# KeyMatrix.net
KiCad netlist of a schematic drawn in Altium Designer
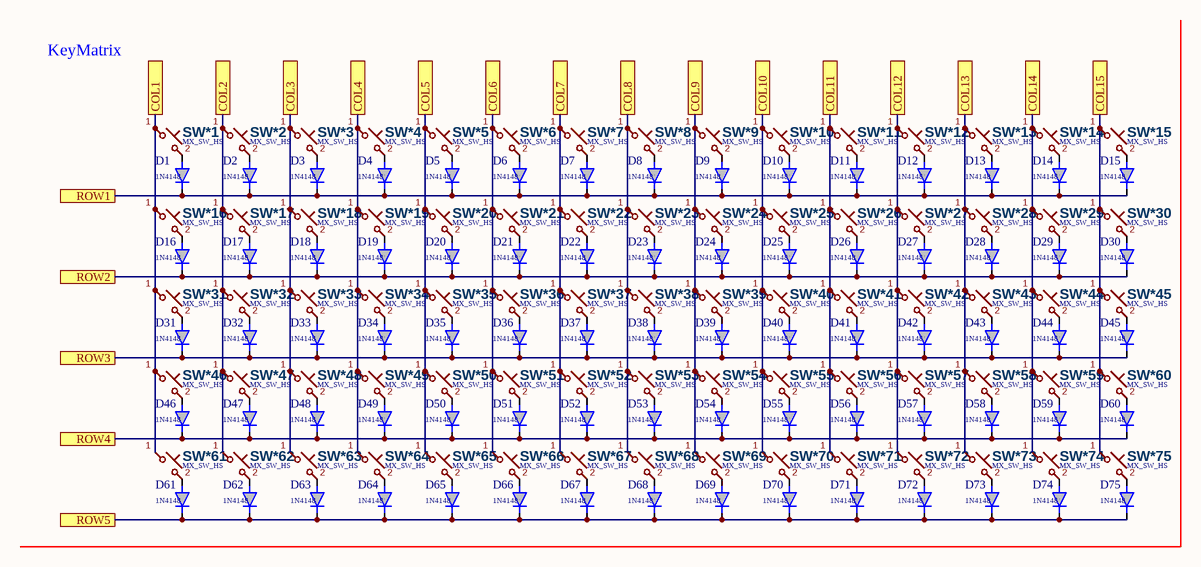
[diagram p0: KeyMatrix.SchDoc]

(export (version "E")
  (design (tool "Eeschema 10.0.6"))
  (components
    (comp (ref "D1")
      (value "1N4148")
      (footprint "SOD3716X135N")
      (description "Small Signal Fast Switching Diode")
      (fields (field (name "MANUFACTURER_PART_NUMBER") "1N4148(SOD-123)"))
      (libsource (lib "1N4148_SOD-123_") (part "1N4148_SOD-123_"))
    )
    (comp (ref "D2")
      (value "1N4148")
      (footprint "SOD3716X135N")
      (description "Small Signal Fast Switching Diode")
      (fields (field (name "MANUFACTURER_PART_NUMBER") "1N4148(SOD-123)"))
      (libsource (lib "1N4148_SOD-123_") (part "1N4148_SOD-123_"))
    )
    (comp (ref "D3")
      (value "1N4148")
      (footprint "SOD3716X135N")
      (description "Small Signal Fast Switching Diode")
      (fields (field (name "MANUFACTURER_PART_NUMBER") "1N4148(SOD-123)"))
      (libsource (lib "1N4148_SOD-123_") (part "1N4148_SOD-123_"))
    )
    (comp (ref "D4")
      (value "1N4148")
      (footprint "SOD3716X135N")
      (description "Small Signal Fast Switching Diode")
      (fields (field (name "MANUFACTURER_PART_NUMBER") "1N4148(SOD-123)"))
      (libsource (lib "1N4148_SOD-123_") (part "1N4148_SOD-123_"))
    )
    (comp (ref "D5")
      (value "1N4148")
      (footprint "SOD3716X135N")
      (description "Small Signal Fast Switching Diode")
      (fields (field (name "MANUFACTURER_PART_NUMBER") "1N4148(SOD-123)"))
      (libsource (lib "1N4148_SOD-123_") (part "1N4148_SOD-123_"))
    )
    (comp (ref "D6")
      (value "1N4148")
      (footprint "SOD3716X135N")
      (description "Small Signal Fast Switching Diode")
      (fields (field (name "MANUFACTURER_PART_NUMBER") "1N4148(SOD-123)"))
      (libsource (lib "1N4148_SOD-123_") (part "1N4148_SOD-123_"))
    )
    (comp (ref "D7")
      (value "1N4148")
      (footprint "SOD3716X135N")
      (description "Small Signal Fast Switching Diode")
      (fields (field (name "MANUFACTURER_PART_NUMBER") "1N4148(SOD-123)"))
      (libsource (lib "1N4148_SOD-123_") (part "1N4148_SOD-123_"))
    )
    (comp (ref "D8")
      (value "1N4148")
      (footprint "SOD3716X135N")
      (description "Small Signal Fast Switching Diode")
      (fields (field (name "MANUFACTURER_PART_NUMBER") "1N4148(SOD-123)"))
      (libsource (lib "1N4148_SOD-123_") (part "1N4148_SOD-123_"))
    )
    (comp (ref "D9")
      (value "1N4148")
      (footprint "SOD3716X135N")
      (description "Small Signal Fast Switching Diode")
      (fields (field (name "MANUFACTURER_PART_NUMBER") "1N4148(SOD-123)"))
      (libsource (lib "1N4148_SOD-123_") (part "1N4148_SOD-123_"))
    )
    (comp (ref "D10")
      (value "1N4148")
      (footprint "SOD3716X135N")
      (description "Small Signal Fast Switching Diode")
      (fields (field (name "MANUFACTURER_PART_NUMBER") "1N4148(SOD-123)"))
      (libsource (lib "1N4148_SOD-123_") (part "1N4148_SOD-123_"))
    )
    (comp (ref "D11")
      (value "1N4148")
      (footprint "SOD3716X135N")
      (description "Small Signal Fast Switching Diode")
      (fields (field (name "MANUFACTURER_PART_NUMBER") "1N4148(SOD-123)"))
      (libsource (lib "1N4148_SOD-123_") (part "1N4148_SOD-123_"))
    )
    (comp (ref "D12")
      (value "1N4148")
      (footprint "SOD3716X135N")
      (description "Small Signal Fast Switching Diode")
      (fields (field (name "MANUFACTURER_PART_NUMBER") "1N4148(SOD-123)"))
      (libsource (lib "1N4148_SOD-123_") (part "1N4148_SOD-123_"))
    )
    (comp (ref "D13")
      (value "1N4148")
      (footprint "SOD3716X135N")
      (description "Small Signal Fast Switching Diode")
      (fields (field (name "MANUFACTURER_PART_NUMBER") "1N4148(SOD-123)"))
      (libsource (lib "1N4148_SOD-123_") (part "1N4148_SOD-123_"))
    )
    (comp (ref "D14")
      (value "1N4148")
      (footprint "SOD3716X135N")
      (description "Small Signal Fast Switching Diode")
      (fields (field (name "MANUFACTURER_PART_NUMBER") "1N4148(SOD-123)"))
      (libsource (lib "1N4148_SOD-123_") (part "1N4148_SOD-123_"))
    )
    (comp (ref "D15")
      (value "1N4148")
      (footprint "SOD3716X135N")
      (description "Small Signal Fast Switching Diode")
      (fields (field (name "MANUFACTURER_PART_NUMBER") "1N4148(SOD-123)"))
      (libsource (lib "1N4148_SOD-123_") (part "1N4148_SOD-123_"))
    )
    (comp (ref "D16")
      (value "1N4148")
      (footprint "SOD3716X135N")
      (description "Small Signal Fast Switching Diode")
      (fields (field (name "MANUFACTURER_PART_NUMBER") "1N4148(SOD-123)"))
      (libsource (lib "1N4148_SOD-123_") (part "1N4148_SOD-123_"))
    )
    (comp (ref "D17")
      (value "1N4148")
      (footprint "SOD3716X135N")
      (description "Small Signal Fast Switching Diode")
      (fields (field (name "MANUFACTURER_PART_NUMBER") "1N4148(SOD-123)"))
      (libsource (lib "1N4148_SOD-123_") (part "1N4148_SOD-123_"))
    )
    (comp (ref "D18")
      (value "1N4148")
      (footprint "SOD3716X135N")
      (description "Small Signal Fast Switching Diode")
      (fields (field (name "MANUFACTURER_PART_NUMBER") "1N4148(SOD-123)"))
      (libsource (lib "1N4148_SOD-123_") (part "1N4148_SOD-123_"))
    )
    (comp (ref "D19")
      (value "1N4148")
      (footprint "SOD3716X135N")
      (description "Small Signal Fast Switching Diode")
      (fields (field (name "MANUFACTURER_PART_NUMBER") "1N4148(SOD-123)"))
      (libsource (lib "1N4148_SOD-123_") (part "1N4148_SOD-123_"))
    )
    (comp (ref "D20")
      (value "1N4148")
      (footprint "SOD3716X135N")
      (description "Small Signal Fast Switching Diode")
      (fields (field (name "MANUFACTURER_PART_NUMBER") "1N4148(SOD-123)"))
      (libsource (lib "1N4148_SOD-123_") (part "1N4148_SOD-123_"))
    )
    (comp (ref "D21")
      (value "1N4148")
      (footprint "SOD3716X135N")
      (description "Small Signal Fast Switching Diode")
      (fields (field (name "MANUFACTURER_PART_NUMBER") "1N4148(SOD-123)"))
      (libsource (lib "1N4148_SOD-123_") (part "1N4148_SOD-123_"))
    )
    (comp (ref "D22")
      (value "1N4148")
      (footprint "SOD3716X135N")
      (description "Small Signal Fast Switching Diode")
      (fields (field (name "MANUFACTURER_PART_NUMBER") "1N4148(SOD-123)"))
      (libsource (lib "1N4148_SOD-123_") (part "1N4148_SOD-123_"))
    )
    (comp (ref "D23")
      (value "1N4148")
      (footprint "SOD3716X135N")
      (description "Small Signal Fast Switching Diode")
      (fields (field (name "MANUFACTURER_PART_NUMBER") "1N4148(SOD-123)"))
      (libsource (lib "1N4148_SOD-123_") (part "1N4148_SOD-123_"))
    )
    (comp (ref "D24")
      (value "1N4148")
      (footprint "SOD3716X135N")
      (description "Small Signal Fast Switching Diode")
      (fields (field (name "MANUFACTURER_PART_NUMBER") "1N4148(SOD-123)"))
      (libsource (lib "1N4148_SOD-123_") (part "1N4148_SOD-123_"))
    )
    (comp (ref "D25")
      (value "1N4148")
      (footprint "SOD3716X135N")
      (description "Small Signal Fast Switching Diode")
      (fields (field (name "MANUFACTURER_PART_NUMBER") "1N4148(SOD-123)"))
      (libsource (lib "1N4148_SOD-123_") (part "1N4148_SOD-123_"))
    )
    (comp (ref "D26")
      (value "1N4148")
      (footprint "SOD3716X135N")
      (description "Small Signal Fast Switching Diode")
      (fields (field (name "MANUFACTURER_PART_NUMBER") "1N4148(SOD-123)"))
      (libsource (lib "1N4148_SOD-123_") (part "1N4148_SOD-123_"))
    )
    (comp (ref "D27")
      (value "1N4148")
      (footprint "SOD3716X135N")
      (description "Small Signal Fast Switching Diode")
      (fields (field (name "MANUFACTURER_PART_NUMBER") "1N4148(SOD-123)"))
      (libsource (lib "1N4148_SOD-123_") (part "1N4148_SOD-123_"))
    )
    (comp (ref "D28")
      (value "1N4148")
      (footprint "SOD3716X135N")
      (description "Small Signal Fast Switching Diode")
      (fields (field (name "MANUFACTURER_PART_NUMBER") "1N4148(SOD-123)"))
      (libsource (lib "1N4148_SOD-123_") (part "1N4148_SOD-123_"))
    )
    (comp (ref "D29")
      (value "1N4148")
      (footprint "SOD3716X135N")
      (description "Small Signal Fast Switching Diode")
      (fields (field (name "MANUFACTURER_PART_NUMBER") "1N4148(SOD-123)"))
      (libsource (lib "1N4148_SOD-123_") (part "1N4148_SOD-123_"))
    )
    (comp (ref "D30")
      (value "1N4148")
      (footprint "SOD3716X135N")
      (description "Small Signal Fast Switching Diode")
      (fields (field (name "MANUFACTURER_PART_NUMBER") "1N4148(SOD-123)"))
      (libsource (lib "1N4148_SOD-123_") (part "1N4148_SOD-123_"))
    )
    (comp (ref "D31")
      (value "1N4148")
      (footprint "SOD3716X135N")
      (description "Small Signal Fast Switching Diode")
      (fields (field (name "MANUFACTURER_PART_NUMBER") "1N4148(SOD-123)"))
      (libsource (lib "1N4148_SOD-123_") (part "1N4148_SOD-123_"))
    )
    (comp (ref "D32")
      (value "1N4148")
      (footprint "SOD3716X135N")
      (description "Small Signal Fast Switching Diode")
      (fields (field (name "MANUFACTURER_PART_NUMBER") "1N4148(SOD-123)"))
      (libsource (lib "1N4148_SOD-123_") (part "1N4148_SOD-123_"))
    )
    (comp (ref "D33")
      (value "1N4148")
      (footprint "SOD3716X135N")
      (description "Small Signal Fast Switching Diode")
      (fields (field (name "MANUFACTURER_PART_NUMBER") "1N4148(SOD-123)"))
      (libsource (lib "1N4148_SOD-123_") (part "1N4148_SOD-123_"))
    )
    (comp (ref "D34")
      (value "1N4148")
      (footprint "SOD3716X135N")
      (description "Small Signal Fast Switching Diode")
      (fields (field (name "MANUFACTURER_PART_NUMBER") "1N4148(SOD-123)"))
      (libsource (lib "1N4148_SOD-123_") (part "1N4148_SOD-123_"))
    )
    (comp (ref "D35")
      (value "1N4148")
      (footprint "SOD3716X135N")
      (description "Small Signal Fast Switching Diode")
      (fields (field (name "MANUFACTURER_PART_NUMBER") "1N4148(SOD-123)"))
      (libsource (lib "1N4148_SOD-123_") (part "1N4148_SOD-123_"))
    )
    (comp (ref "D36")
      (value "1N4148")
      (footprint "SOD3716X135N")
      (description "Small Signal Fast Switching Diode")
      (fields (field (name "MANUFACTURER_PART_NUMBER") "1N4148(SOD-123)"))
      (libsource (lib "1N4148_SOD-123_") (part "1N4148_SOD-123_"))
    )
    (comp (ref "D37")
      (value "1N4148")
      (footprint "SOD3716X135N")
      (description "Small Signal Fast Switching Diode")
      (fields (field (name "MANUFACTURER_PART_NUMBER") "1N4148(SOD-123)"))
      (libsource (lib "1N4148_SOD-123_") (part "1N4148_SOD-123_"))
    )
    (comp (ref "D38")
      (value "1N4148")
      (footprint "SOD3716X135N")
      (description "Small Signal Fast Switching Diode")
      (fields (field (name "MANUFACTURER_PART_NUMBER") "1N4148(SOD-123)"))
      (libsource (lib "1N4148_SOD-123_") (part "1N4148_SOD-123_"))
    )
    (comp (ref "D39")
      (value "1N4148")
      (footprint "SOD3716X135N")
      (description "Small Signal Fast Switching Diode")
      (fields (field (name "MANUFACTURER_PART_NUMBER") "1N4148(SOD-123)"))
      (libsource (lib "1N4148_SOD-123_") (part "1N4148_SOD-123_"))
    )
    (comp (ref "D40")
      (value "1N4148")
      (footprint "SOD3716X135N")
      (description "Small Signal Fast Switching Diode")
      (fields (field (name "MANUFACTURER_PART_NUMBER") "1N4148(SOD-123)"))
      (libsource (lib "1N4148_SOD-123_") (part "1N4148_SOD-123_"))
    )
    (comp (ref "D41")
      (value "1N4148")
      (footprint "SOD3716X135N")
      (description "Small Signal Fast Switching Diode")
      (fields (field (name "MANUFACTURER_PART_NUMBER") "1N4148(SOD-123)"))
      (libsource (lib "1N4148_SOD-123_") (part "1N4148_SOD-123_"))
    )
    (comp (ref "D42")
      (value "1N4148")
      (footprint "SOD3716X135N")
      (description "Small Signal Fast Switching Diode")
      (fields (field (name "MANUFACTURER_PART_NUMBER") "1N4148(SOD-123)"))
      (libsource (lib "1N4148_SOD-123_") (part "1N4148_SOD-123_"))
    )
    (comp (ref "D43")
      (value "1N4148")
      (footprint "SOD3716X135N")
      (description "Small Signal Fast Switching Diode")
      (fields (field (name "MANUFACTURER_PART_NUMBER") "1N4148(SOD-123)"))
      (libsource (lib "1N4148_SOD-123_") (part "1N4148_SOD-123_"))
    )
    (comp (ref "D44")
      (value "1N4148")
      (footprint "SOD3716X135N")
      (description "Small Signal Fast Switching Diode")
      (fields (field (name "MANUFACTURER_PART_NUMBER") "1N4148(SOD-123)"))
      (libsource (lib "1N4148_SOD-123_") (part "1N4148_SOD-123_"))
    )
    (comp (ref "D45")
      (value "1N4148")
      (footprint "SOD3716X135N")
      (description "Small Signal Fast Switching Diode")
      (fields (field (name "MANUFACTURER_PART_NUMBER") "1N4148(SOD-123)"))
      (libsource (lib "1N4148_SOD-123_") (part "1N4148_SOD-123_"))
    )
    (comp (ref "D46")
      (value "1N4148")
      (footprint "SOD3716X135N")
      (description "Small Signal Fast Switching Diode")
      (fields (field (name "MANUFACTURER_PART_NUMBER") "1N4148(SOD-123)"))
      (libsource (lib "1N4148_SOD-123_") (part "1N4148_SOD-123_"))
    )
    (comp (ref "D47")
      (value "1N4148")
      (footprint "SOD3716X135N")
      (description "Small Signal Fast Switching Diode")
      (fields (field (name "MANUFACTURER_PART_NUMBER") "1N4148(SOD-123)"))
      (libsource (lib "1N4148_SOD-123_") (part "1N4148_SOD-123_"))
    )
    (comp (ref "D48")
      (value "1N4148")
      (footprint "SOD3716X135N")
      (description "Small Signal Fast Switching Diode")
      (fields (field (name "MANUFACTURER_PART_NUMBER") "1N4148(SOD-123)"))
      (libsource (lib "1N4148_SOD-123_") (part "1N4148_SOD-123_"))
    )
    (comp (ref "D49")
      (value "1N4148")
      (footprint "SOD3716X135N")
      (description "Small Signal Fast Switching Diode")
      (fields (field (name "MANUFACTURER_PART_NUMBER") "1N4148(SOD-123)"))
      (libsource (lib "1N4148_SOD-123_") (part "1N4148_SOD-123_"))
    )
    (comp (ref "D50")
      (value "1N4148")
      (footprint "SOD3716X135N")
      (description "Small Signal Fast Switching Diode")
      (fields (field (name "MANUFACTURER_PART_NUMBER") "1N4148(SOD-123)"))
      (libsource (lib "1N4148_SOD-123_") (part "1N4148_SOD-123_"))
    )
    (comp (ref "D51")
      (value "1N4148")
      (footprint "SOD3716X135N")
      (description "Small Signal Fast Switching Diode")
      (fields (field (name "MANUFACTURER_PART_NUMBER") "1N4148(SOD-123)"))
      (libsource (lib "1N4148_SOD-123_") (part "1N4148_SOD-123_"))
    )
    (comp (ref "D52")
      (value "1N4148")
      (footprint "SOD3716X135N")
      (description "Small Signal Fast Switching Diode")
      (fields (field (name "MANUFACTURER_PART_NUMBER") "1N4148(SOD-123)"))
      (libsource (lib "1N4148_SOD-123_") (part "1N4148_SOD-123_"))
    )
    (comp (ref "D53")
      (value "1N4148")
      (footprint "SOD3716X135N")
      (description "Small Signal Fast Switching Diode")
      (fields (field (name "MANUFACTURER_PART_NUMBER") "1N4148(SOD-123)"))
      (libsource (lib "1N4148_SOD-123_") (part "1N4148_SOD-123_"))
    )
    (comp (ref "D54")
      (value "1N4148")
      (footprint "SOD3716X135N")
      (description "Small Signal Fast Switching Diode")
      (fields (field (name "MANUFACTURER_PART_NUMBER") "1N4148(SOD-123)"))
      (libsource (lib "1N4148_SOD-123_") (part "1N4148_SOD-123_"))
    )
    (comp (ref "D55")
      (value "1N4148")
      (footprint "SOD3716X135N")
      (description "Small Signal Fast Switching Diode")
      (fields (field (name "MANUFACTURER_PART_NUMBER") "1N4148(SOD-123)"))
      (libsource (lib "1N4148_SOD-123_") (part "1N4148_SOD-123_"))
    )
    (comp (ref "D56")
      (value "1N4148")
      (footprint "SOD3716X135N")
      (description "Small Signal Fast Switching Diode")
      (fields (field (name "MANUFACTURER_PART_NUMBER") "1N4148(SOD-123)"))
      (libsource (lib "1N4148_SOD-123_") (part "1N4148_SOD-123_"))
    )
    (comp (ref "D57")
      (value "1N4148")
      (footprint "SOD3716X135N")
      (description "Small Signal Fast Switching Diode")
      (fields (field (name "MANUFACTURER_PART_NUMBER") "1N4148(SOD-123)"))
      (libsource (lib "1N4148_SOD-123_") (part "1N4148_SOD-123_"))
    )
    (comp (ref "D58")
      (value "1N4148")
      (footprint "SOD3716X135N")
      (description "Small Signal Fast Switching Diode")
      (fields (field (name "MANUFACTURER_PART_NUMBER") "1N4148(SOD-123)"))
      (libsource (lib "1N4148_SOD-123_") (part "1N4148_SOD-123_"))
    )
    (comp (ref "D59")
      (value "1N4148")
      (footprint "SOD3716X135N")
      (description "Small Signal Fast Switching Diode")
      (fields (field (name "MANUFACTURER_PART_NUMBER") "1N4148(SOD-123)"))
      (libsource (lib "1N4148_SOD-123_") (part "1N4148_SOD-123_"))
    )
    (comp (ref "D60")
      (value "1N4148")
      (footprint "SOD3716X135N")
      (description "Small Signal Fast Switching Diode")
      (fields (field (name "MANUFACTURER_PART_NUMBER") "1N4148(SOD-123)"))
      (libsource (lib "1N4148_SOD-123_") (part "1N4148_SOD-123_"))
    )
    (comp (ref "D61")
      (value "1N4148")
      (footprint "SOD3716X135N")
      (description "Small Signal Fast Switching Diode")
      (fields (field (name "MANUFACTURER_PART_NUMBER") "1N4148(SOD-123)"))
      (libsource (lib "1N4148_SOD-123_") (part "1N4148_SOD-123_"))
    )
    (comp (ref "D62")
      (value "1N4148")
      (footprint "SOD3716X135N")
      (description "Small Signal Fast Switching Diode")
      (fields (field (name "MANUFACTURER_PART_NUMBER") "1N4148(SOD-123)"))
      (libsource (lib "1N4148_SOD-123_") (part "1N4148_SOD-123_"))
    )
    (comp (ref "D63")
      (value "1N4148")
      (footprint "SOD3716X135N")
      (description "Small Signal Fast Switching Diode")
      (fields (field (name "MANUFACTURER_PART_NUMBER") "1N4148(SOD-123)"))
      (libsource (lib "1N4148_SOD-123_") (part "1N4148_SOD-123_"))
    )
    (comp (ref "D64")
      (value "1N4148")
      (footprint "SOD3716X135N")
      (description "Small Signal Fast Switching Diode")
      (fields (field (name "MANUFACTURER_PART_NUMBER") "1N4148(SOD-123)"))
      (libsource (lib "1N4148_SOD-123_") (part "1N4148_SOD-123_"))
    )
    (comp (ref "D65")
      (value "1N4148")
      (footprint "SOD3716X135N")
      (description "Small Signal Fast Switching Diode")
      (fields (field (name "MANUFACTURER_PART_NUMBER") "1N4148(SOD-123)"))
      (libsource (lib "1N4148_SOD-123_") (part "1N4148_SOD-123_"))
    )
    (comp (ref "D66")
      (value "1N4148")
      (footprint "SOD3716X135N")
      (description "Small Signal Fast Switching Diode")
      (fields (field (name "MANUFACTURER_PART_NUMBER") "1N4148(SOD-123)"))
      (libsource (lib "1N4148_SOD-123_") (part "1N4148_SOD-123_"))
    )
    (comp (ref "D67")
      (value "1N4148")
      (footprint "SOD3716X135N")
      (description "Small Signal Fast Switching Diode")
      (fields (field (name "MANUFACTURER_PART_NUMBER") "1N4148(SOD-123)"))
      (libsource (lib "1N4148_SOD-123_") (part "1N4148_SOD-123_"))
    )
    (comp (ref "D68")
      (value "1N4148")
      (footprint "SOD3716X135N")
      (description "Small Signal Fast Switching Diode")
      (fields (field (name "MANUFACTURER_PART_NUMBER") "1N4148(SOD-123)"))
      (libsource (lib "1N4148_SOD-123_") (part "1N4148_SOD-123_"))
    )
    (comp (ref "D69")
      (value "1N4148")
      (footprint "SOD3716X135N")
      (description "Small Signal Fast Switching Diode")
      (fields (field (name "MANUFACTURER_PART_NUMBER") "1N4148(SOD-123)"))
      (libsource (lib "1N4148_SOD-123_") (part "1N4148_SOD-123_"))
    )
    (comp (ref "D70")
      (value "1N4148")
      (footprint "SOD3716X135N")
      (description "Small Signal Fast Switching Diode")
      (fields (field (name "MANUFACTURER_PART_NUMBER") "1N4148(SOD-123)"))
      (libsource (lib "1N4148_SOD-123_") (part "1N4148_SOD-123_"))
    )
    (comp (ref "D71")
      (value "1N4148")
      (footprint "SOD3716X135N")
      (description "Small Signal Fast Switching Diode")
      (fields (field (name "MANUFACTURER_PART_NUMBER") "1N4148(SOD-123)"))
      (libsource (lib "1N4148_SOD-123_") (part "1N4148_SOD-123_"))
    )
    (comp (ref "D72")
      (value "1N4148")
      (footprint "SOD3716X135N")
      (description "Small Signal Fast Switching Diode")
      (fields (field (name "MANUFACTURER_PART_NUMBER") "1N4148(SOD-123)"))
      (libsource (lib "1N4148_SOD-123_") (part "1N4148_SOD-123_"))
    )
    (comp (ref "D73")
      (value "1N4148")
      (footprint "SOD3716X135N")
      (description "Small Signal Fast Switching Diode")
      (fields (field (name "MANUFACTURER_PART_NUMBER") "1N4148(SOD-123)"))
      (libsource (lib "1N4148_SOD-123_") (part "1N4148_SOD-123_"))
    )
    (comp (ref "D74")
      (value "1N4148")
      (footprint "SOD3716X135N")
      (description "Small Signal Fast Switching Diode")
      (fields (field (name "MANUFACTURER_PART_NUMBER") "1N4148(SOD-123)"))
      (libsource (lib "1N4148_SOD-123_") (part "1N4148_SOD-123_"))
    )
    (comp (ref "D75")
      (value "1N4148")
      (footprint "SOD3716X135N")
      (description "Small Signal Fast Switching Diode")
      (fields (field (name "MANUFACTURER_PART_NUMBER") "1N4148(SOD-123)"))
      (libsource (lib "1N4148_SOD-123_") (part "1N4148_SOD-123_"))
    )
    (comp (ref "SW*1") (value "MX_SW_HS") (libsource (lib "marbastlib-mx") (part "MX_SW_HS")))
    (comp (ref "SW*2") (value "MX_SW_HS") (libsource (lib "marbastlib-mx") (part "MX_SW_HS")))
    (comp (ref "SW*3") (value "MX_SW_HS") (libsource (lib "marbastlib-mx") (part "MX_SW_HS")))
    (comp (ref "SW*4") (value "MX_SW_HS") (libsource (lib "marbastlib-mx") (part "MX_SW_HS")))
    (comp (ref "SW*5") (value "MX_SW_HS") (libsource (lib "marbastlib-mx") (part "MX_SW_HS")))
    (comp (ref "SW*6") (value "MX_SW_HS") (libsource (lib "marbastlib-mx") (part "MX_SW_HS")))
    (comp (ref "SW*7") (value "MX_SW_HS") (libsource (lib "marbastlib-mx") (part "MX_SW_HS")))
    (comp (ref "SW*8") (value "MX_SW_HS") (libsource (lib "marbastlib-mx") (part "MX_SW_HS")))
    (comp (ref "SW*9") (value "MX_SW_HS") (libsource (lib "marbastlib-mx") (part "MX_SW_HS")))
    (comp (ref "SW*10") (value "MX_SW_HS") (libsource (lib "marbastlib-mx") (part "MX_SW_HS")))
    (comp (ref "SW*11") (value "MX_SW_HS") (libsource (lib "marbastlib-mx") (part "MX_SW_HS")))
    (comp (ref "SW*12") (value "MX_SW_HS") (libsource (lib "marbastlib-mx") (part "MX_SW_HS")))
    (comp (ref "SW*13") (value "MX_SW_HS") (libsource (lib "marbastlib-mx") (part "MX_SW_HS")))
    (comp (ref "SW*14") (value "MX_SW_HS") (libsource (lib "marbastlib-mx") (part "MX_SW_HS")))
    (comp (ref "SW*15") (value "MX_SW_HS") (libsource (lib "marbastlib-mx") (part "MX_SW_HS")))
    (comp (ref "SW*16") (value "MX_SW_HS") (libsource (lib "marbastlib-mx") (part "MX_SW_HS")))
    (comp (ref "SW*17") (value "MX_SW_HS") (libsource (lib "marbastlib-mx") (part "MX_SW_HS")))
    (comp (ref "SW*18") (value "MX_SW_HS") (libsource (lib "marbastlib-mx") (part "MX_SW_HS")))
    (comp (ref "SW*19") (value "MX_SW_HS") (libsource (lib "marbastlib-mx") (part "MX_SW_HS")))
    (comp (ref "SW*20") (value "MX_SW_HS") (libsource (lib "marbastlib-mx") (part "MX_SW_HS")))
    (comp (ref "SW*21") (value "MX_SW_HS") (libsource (lib "marbastlib-mx") (part "MX_SW_HS")))
    (comp (ref "SW*22") (value "MX_SW_HS") (libsource (lib "marbastlib-mx") (part "MX_SW_HS")))
    (comp (ref "SW*23") (value "MX_SW_HS") (libsource (lib "marbastlib-mx") (part "MX_SW_HS")))
    (comp (ref "SW*24") (value "MX_SW_HS") (libsource (lib "marbastlib-mx") (part "MX_SW_HS")))
    (comp (ref "SW*25") (value "MX_SW_HS") (libsource (lib "marbastlib-mx") (part "MX_SW_HS")))
    (comp (ref "SW*26") (value "MX_SW_HS") (libsource (lib "marbastlib-mx") (part "MX_SW_HS")))
    (comp (ref "SW*27") (value "MX_SW_HS") (libsource (lib "marbastlib-mx") (part "MX_SW_HS")))
    (comp (ref "SW*28") (value "MX_SW_HS") (libsource (lib "marbastlib-mx") (part "MX_SW_HS")))
    (comp (ref "SW*29") (value "MX_SW_HS") (libsource (lib "marbastlib-mx") (part "MX_SW_HS")))
    (comp (ref "SW*30") (value "MX_SW_HS") (libsource (lib "marbastlib-mx") (part "MX_SW_HS")))
    (comp (ref "SW*31") (value "MX_SW_HS") (libsource (lib "marbastlib-mx") (part "MX_SW_HS")))
    (comp (ref "SW*32") (value "MX_SW_HS") (libsource (lib "marbastlib-mx") (part "MX_SW_HS")))
    (comp (ref "SW*33") (value "MX_SW_HS") (libsource (lib "marbastlib-mx") (part "MX_SW_HS")))
    (comp (ref "SW*34") (value "MX_SW_HS") (libsource (lib "marbastlib-mx") (part "MX_SW_HS")))
    (comp (ref "SW*35") (value "MX_SW_HS") (libsource (lib "marbastlib-mx") (part "MX_SW_HS")))
    (comp (ref "SW*36") (value "MX_SW_HS") (libsource (lib "marbastlib-mx") (part "MX_SW_HS")))
    (comp (ref "SW*37") (value "MX_SW_HS") (libsource (lib "marbastlib-mx") (part "MX_SW_HS")))
    (comp (ref "SW*38") (value "MX_SW_HS") (libsource (lib "marbastlib-mx") (part "MX_SW_HS")))
    (comp (ref "SW*39") (value "MX_SW_HS") (libsource (lib "marbastlib-mx") (part "MX_SW_HS")))
    (comp (ref "SW*40") (value "MX_SW_HS") (libsource (lib "marbastlib-mx") (part "MX_SW_HS")))
    (comp (ref "SW*41") (value "MX_SW_HS") (libsource (lib "marbastlib-mx") (part "MX_SW_HS")))
    (comp (ref "SW*42") (value "MX_SW_HS") (libsource (lib "marbastlib-mx") (part "MX_SW_HS")))
    (comp (ref "SW*43") (value "MX_SW_HS") (libsource (lib "marbastlib-mx") (part "MX_SW_HS")))
    (comp (ref "SW*44") (value "MX_SW_HS") (libsource (lib "marbastlib-mx") (part "MX_SW_HS")))
    (comp (ref "SW*45") (value "MX_SW_HS") (libsource (lib "marbastlib-mx") (part "MX_SW_HS")))
    (comp (ref "SW*46") (value "MX_SW_HS") (libsource (lib "marbastlib-mx") (part "MX_SW_HS")))
    (comp (ref "SW*47") (value "MX_SW_HS") (libsource (lib "marbastlib-mx") (part "MX_SW_HS")))
    (comp (ref "SW*48") (value "MX_SW_HS") (libsource (lib "marbastlib-mx") (part "MX_SW_HS")))
    (comp (ref "SW*49") (value "MX_SW_HS") (libsource (lib "marbastlib-mx") (part "MX_SW_HS")))
    (comp (ref "SW*50") (value "MX_SW_HS") (libsource (lib "marbastlib-mx") (part "MX_SW_HS")))
    (comp (ref "SW*51") (value "MX_SW_HS") (libsource (lib "marbastlib-mx") (part "MX_SW_HS")))
    (comp (ref "SW*52") (value "MX_SW_HS") (libsource (lib "marbastlib-mx") (part "MX_SW_HS")))
    (comp (ref "SW*53") (value "MX_SW_HS") (libsource (lib "marbastlib-mx") (part "MX_SW_HS")))
    (comp (ref "SW*54") (value "MX_SW_HS") (libsource (lib "marbastlib-mx") (part "MX_SW_HS")))
    (comp (ref "SW*55") (value "MX_SW_HS") (libsource (lib "marbastlib-mx") (part "MX_SW_HS")))
    (comp (ref "SW*56") (value "MX_SW_HS") (libsource (lib "marbastlib-mx") (part "MX_SW_HS")))
    (comp (ref "SW*57") (value "MX_SW_HS") (libsource (lib "marbastlib-mx") (part "MX_SW_HS")))
    (comp (ref "SW*58") (value "MX_SW_HS") (libsource (lib "marbastlib-mx") (part "MX_SW_HS")))
    (comp (ref "SW*59") (value "MX_SW_HS") (libsource (lib "marbastlib-mx") (part "MX_SW_HS")))
    (comp (ref "SW*60") (value "MX_SW_HS") (libsource (lib "marbastlib-mx") (part "MX_SW_HS")))
    (comp (ref "SW*61") (value "MX_SW_HS") (libsource (lib "marbastlib-mx") (part "MX_SW_HS")))
    (comp (ref "SW*62") (value "MX_SW_HS") (libsource (lib "marbastlib-mx") (part "MX_SW_HS")))
    (comp (ref "SW*63") (value "MX_SW_HS") (libsource (lib "marbastlib-mx") (part "MX_SW_HS")))
    (comp (ref "SW*64") (value "MX_SW_HS") (libsource (lib "marbastlib-mx") (part "MX_SW_HS")))
    (comp (ref "SW*65") (value "MX_SW_HS") (libsource (lib "marbastlib-mx") (part "MX_SW_HS")))
    (comp (ref "SW*66") (value "MX_SW_HS") (libsource (lib "marbastlib-mx") (part "MX_SW_HS")))
    (comp (ref "SW*67") (value "MX_SW_HS") (libsource (lib "marbastlib-mx") (part "MX_SW_HS")))
    (comp (ref "SW*68") (value "MX_SW_HS") (libsource (lib "marbastlib-mx") (part "MX_SW_HS")))
    (comp (ref "SW*69") (value "MX_SW_HS") (libsource (lib "marbastlib-mx") (part "MX_SW_HS")))
    (comp (ref "SW*70") (value "MX_SW_HS") (libsource (lib "marbastlib-mx") (part "MX_SW_HS")))
    (comp (ref "SW*71") (value "MX_SW_HS") (libsource (lib "marbastlib-mx") (part "MX_SW_HS")))
    (comp (ref "SW*72") (value "MX_SW_HS") (libsource (lib "marbastlib-mx") (part "MX_SW_HS")))
    (comp (ref "SW*73") (value "MX_SW_HS") (libsource (lib "marbastlib-mx") (part "MX_SW_HS")))
    (comp (ref "SW*74") (value "MX_SW_HS") (libsource (lib "marbastlib-mx") (part "MX_SW_HS")))
    (comp (ref "SW*75") (value "MX_SW_HS") (libsource (lib "marbastlib-mx") (part "MX_SW_HS")))
  )
  (nets
    (net (code "1") (name "/COL1") (class "Default")
      (node (ref "SW*1") (pin "1") (pinfunction "1_1") (pintype "passive"))
      (node (ref "SW*16") (pin "1") (pinfunction "1_1") (pintype "passive"))
      (node (ref "SW*31") (pin "1") (pinfunction "1_1") (pintype "passive"))
      (node (ref "SW*46") (pin "1") (pinfunction "1_1") (pintype "passive"))
      (node (ref "SW*61") (pin "1") (pinfunction "1_1") (pintype "passive"))
    )
    (net (code "2") (name "/COL2") (class "Default")
      (node (ref "SW*17") (pin "1") (pinfunction "1_1") (pintype "passive"))
      (node (ref "SW*2") (pin "1") (pinfunction "1_1") (pintype "passive"))
      (node (ref "SW*32") (pin "1") (pinfunction "1_1") (pintype "passive"))
      (node (ref "SW*47") (pin "1") (pinfunction "1_1") (pintype "passive"))
      (node (ref "SW*62") (pin "1") (pinfunction "1_1") (pintype "passive"))
    )
    (net (code "3") (name "/COL3") (class "Default")
      (node (ref "SW*18") (pin "1") (pinfunction "1_1") (pintype "passive"))
      (node (ref "SW*3") (pin "1") (pinfunction "1_1") (pintype "passive"))
      (node (ref "SW*33") (pin "1") (pinfunction "1_1") (pintype "passive"))
      (node (ref "SW*48") (pin "1") (pinfunction "1_1") (pintype "passive"))
      (node (ref "SW*63") (pin "1") (pinfunction "1_1") (pintype "passive"))
    )
    (net (code "4") (name "/COL4") (class "Default")
      (node (ref "SW*19") (pin "1") (pinfunction "1_1") (pintype "passive"))
      (node (ref "SW*34") (pin "1") (pinfunction "1_1") (pintype "passive"))
      (node (ref "SW*4") (pin "1") (pinfunction "1_1") (pintype "passive"))
      (node (ref "SW*49") (pin "1") (pinfunction "1_1") (pintype "passive"))
      (node (ref "SW*64") (pin "1") (pinfunction "1_1") (pintype "passive"))
    )
    (net (code "5") (name "/COL5") (class "Default")
      (node (ref "SW*20") (pin "1") (pinfunction "1_1") (pintype "passive"))
      (node (ref "SW*35") (pin "1") (pinfunction "1_1") (pintype "passive"))
      (node (ref "SW*5") (pin "1") (pinfunction "1_1") (pintype "passive"))
      (node (ref "SW*50") (pin "1") (pinfunction "1_1") (pintype "passive"))
      (node (ref "SW*65") (pin "1") (pinfunction "1_1") (pintype "passive"))
    )
    (net (code "6") (name "/COL6") (class "Default")
      (node (ref "SW*21") (pin "1") (pinfunction "1_1") (pintype "passive"))
      (node (ref "SW*36") (pin "1") (pinfunction "1_1") (pintype "passive"))
      (node (ref "SW*51") (pin "1") (pinfunction "1_1") (pintype "passive"))
      (node (ref "SW*6") (pin "1") (pinfunction "1_1") (pintype "passive"))
      (node (ref "SW*66") (pin "1") (pinfunction "1_1") (pintype "passive"))
    )
    (net (code "7") (name "/COL7") (class "Default")
      (node (ref "SW*22") (pin "1") (pinfunction "1_1") (pintype "passive"))
      (node (ref "SW*37") (pin "1") (pinfunction "1_1") (pintype "passive"))
      (node (ref "SW*52") (pin "1") (pinfunction "1_1") (pintype "passive"))
      (node (ref "SW*67") (pin "1") (pinfunction "1_1") (pintype "passive"))
      (node (ref "SW*7") (pin "1") (pinfunction "1_1") (pintype "passive"))
    )
    (net (code "8") (name "/COL8") (class "Default")
      (node (ref "SW*23") (pin "1") (pinfunction "1_1") (pintype "passive"))
      (node (ref "SW*38") (pin "1") (pinfunction "1_1") (pintype "passive"))
      (node (ref "SW*53") (pin "1") (pinfunction "1_1") (pintype "passive"))
      (node (ref "SW*68") (pin "1") (pinfunction "1_1") (pintype "passive"))
      (node (ref "SW*8") (pin "1") (pinfunction "1_1") (pintype "passive"))
    )
    (net (code "9") (name "/COL9") (class "Default")
      (node (ref "SW*24") (pin "1") (pinfunction "1_1") (pintype "passive"))
      (node (ref "SW*39") (pin "1") (pinfunction "1_1") (pintype "passive"))
      (node (ref "SW*54") (pin "1") (pinfunction "1_1") (pintype "passive"))
      (node (ref "SW*69") (pin "1") (pinfunction "1_1") (pintype "passive"))
      (node (ref "SW*9") (pin "1") (pinfunction "1_1") (pintype "passive"))
    )
    (net (code "10") (name "/COL10") (class "Default")
      (node (ref "SW*10") (pin "1") (pinfunction "1_1") (pintype "passive"))
      (node (ref "SW*25") (pin "1") (pinfunction "1_1") (pintype "passive"))
      (node (ref "SW*40") (pin "1") (pinfunction "1_1") (pintype "passive"))
      (node (ref "SW*55") (pin "1") (pinfunction "1_1") (pintype "passive"))
      (node (ref "SW*70") (pin "1") (pinfunction "1_1") (pintype "passive"))
    )
    (net (code "11") (name "/COL11") (class "Default")
      (node (ref "SW*11") (pin "1") (pinfunction "1_1") (pintype "passive"))
      (node (ref "SW*26") (pin "1") (pinfunction "1_1") (pintype "passive"))
      (node (ref "SW*41") (pin "1") (pinfunction "1_1") (pintype "passive"))
      (node (ref "SW*56") (pin "1") (pinfunction "1_1") (pintype "passive"))
      (node (ref "SW*71") (pin "1") (pinfunction "1_1") (pintype "passive"))
    )
    (net (code "12") (name "/COL12") (class "Default")
      (node (ref "SW*12") (pin "1") (pinfunction "1_1") (pintype "passive"))
      (node (ref "SW*27") (pin "1") (pinfunction "1_1") (pintype "passive"))
      (node (ref "SW*42") (pin "1") (pinfunction "1_1") (pintype "passive"))
      (node (ref "SW*57") (pin "1") (pinfunction "1_1") (pintype "passive"))
      (node (ref "SW*72") (pin "1") (pinfunction "1_1") (pintype "passive"))
    )
    (net (code "13") (name "/COL13") (class "Default")
      (node (ref "SW*13") (pin "1") (pinfunction "1_1") (pintype "passive"))
      (node (ref "SW*28") (pin "1") (pinfunction "1_1") (pintype "passive"))
      (node (ref "SW*43") (pin "1") (pinfunction "1_1") (pintype "passive"))
      (node (ref "SW*58") (pin "1") (pinfunction "1_1") (pintype "passive"))
      (node (ref "SW*73") (pin "1") (pinfunction "1_1") (pintype "passive"))
    )
    (net (code "14") (name "/COL14") (class "Default")
      (node (ref "SW*14") (pin "1") (pinfunction "1_1") (pintype "passive"))
      (node (ref "SW*29") (pin "1") (pinfunction "1_1") (pintype "passive"))
      (node (ref "SW*44") (pin "1") (pinfunction "1_1") (pintype "passive"))
      (node (ref "SW*59") (pin "1") (pinfunction "1_1") (pintype "passive"))
      (node (ref "SW*74") (pin "1") (pinfunction "1_1") (pintype "passive"))
    )
    (net (code "15") (name "/COL15") (class "Default")
      (node (ref "SW*15") (pin "1") (pinfunction "1_1") (pintype "passive"))
      (node (ref "SW*30") (pin "1") (pinfunction "1_1") (pintype "passive"))
      (node (ref "SW*45") (pin "1") (pinfunction "1_1") (pintype "passive"))
      (node (ref "SW*60") (pin "1") (pinfunction "1_1") (pintype "passive"))
      (node (ref "SW*75") (pin "1") (pinfunction "1_1") (pintype "passive"))
    )
    (net (code "16") (name "/ROW1") (class "Default")
      (node (ref "D1") (pin "1") (pinfunction "A_1") (pintype "passive"))
      (node (ref "D10") (pin "1") (pinfunction "A_1") (pintype "passive"))
      (node (ref "D11") (pin "1") (pinfunction "A_1") (pintype "passive"))
      (node (ref "D12") (pin "1") (pinfunction "A_1") (pintype "passive"))
      (node (ref "D13") (pin "1") (pinfunction "A_1") (pintype "passive"))
      (node (ref "D14") (pin "1") (pinfunction "A_1") (pintype "passive"))
      (node (ref "D15") (pin "1") (pinfunction "A_1") (pintype "passive"))
      (node (ref "D2") (pin "1") (pinfunction "A_1") (pintype "passive"))
      (node (ref "D3") (pin "1") (pinfunction "A_1") (pintype "passive"))
      (node (ref "D4") (pin "1") (pinfunction "A_1") (pintype "passive"))
      (node (ref "D5") (pin "1") (pinfunction "A_1") (pintype "passive"))
      (node (ref "D6") (pin "1") (pinfunction "A_1") (pintype "passive"))
      (node (ref "D7") (pin "1") (pinfunction "A_1") (pintype "passive"))
      (node (ref "D8") (pin "1") (pinfunction "A_1") (pintype "passive"))
      (node (ref "D9") (pin "1") (pinfunction "A_1") (pintype "passive"))
    )
    (net (code "17") (name "/ROW2") (class "Default")
      (node (ref "D16") (pin "1") (pinfunction "A_1") (pintype "passive"))
      (node (ref "D17") (pin "1") (pinfunction "A_1") (pintype "passive"))
      (node (ref "D18") (pin "1") (pinfunction "A_1") (pintype "passive"))
      (node (ref "D19") (pin "1") (pinfunction "A_1") (pintype "passive"))
      (node (ref "D20") (pin "1") (pinfunction "A_1") (pintype "passive"))
      (node (ref "D21") (pin "1") (pinfunction "A_1") (pintype "passive"))
      (node (ref "D22") (pin "1") (pinfunction "A_1") (pintype "passive"))
      (node (ref "D23") (pin "1") (pinfunction "A_1") (pintype "passive"))
      (node (ref "D24") (pin "1") (pinfunction "A_1") (pintype "passive"))
      (node (ref "D25") (pin "1") (pinfunction "A_1") (pintype "passive"))
      (node (ref "D26") (pin "1") (pinfunction "A_1") (pintype "passive"))
      (node (ref "D27") (pin "1") (pinfunction "A_1") (pintype "passive"))
      (node (ref "D28") (pin "1") (pinfunction "A_1") (pintype "passive"))
      (node (ref "D29") (pin "1") (pinfunction "A_1") (pintype "passive"))
      (node (ref "D30") (pin "1") (pinfunction "A_1") (pintype "passive"))
    )
    (net (code "18") (name "/ROW3") (class "Default")
      (node (ref "D31") (pin "1") (pinfunction "A_1") (pintype "passive"))
      (node (ref "D32") (pin "1") (pinfunction "A_1") (pintype "passive"))
      (node (ref "D33") (pin "1") (pinfunction "A_1") (pintype "passive"))
      (node (ref "D34") (pin "1") (pinfunction "A_1") (pintype "passive"))
      (node (ref "D35") (pin "1") (pinfunction "A_1") (pintype "passive"))
      (node (ref "D36") (pin "1") (pinfunction "A_1") (pintype "passive"))
      (node (ref "D37") (pin "1") (pinfunction "A_1") (pintype "passive"))
      (node (ref "D38") (pin "1") (pinfunction "A_1") (pintype "passive"))
      (node (ref "D39") (pin "1") (pinfunction "A_1") (pintype "passive"))
      (node (ref "D40") (pin "1") (pinfunction "A_1") (pintype "passive"))
      (node (ref "D41") (pin "1") (pinfunction "A_1") (pintype "passive"))
      (node (ref "D42") (pin "1") (pinfunction "A_1") (pintype "passive"))
      (node (ref "D43") (pin "1") (pinfunction "A_1") (pintype "passive"))
      (node (ref "D44") (pin "1") (pinfunction "A_1") (pintype "passive"))
      (node (ref "D45") (pin "1") (pinfunction "A_1") (pintype "passive"))
    )
    (net (code "19") (name "/ROW4") (class "Default")
      (node (ref "D46") (pin "1") (pinfunction "A_1") (pintype "passive"))
      (node (ref "D47") (pin "1") (pinfunction "A_1") (pintype "passive"))
      (node (ref "D48") (pin "1") (pinfunction "A_1") (pintype "passive"))
      (node (ref "D49") (pin "1") (pinfunction "A_1") (pintype "passive"))
      (node (ref "D50") (pin "1") (pinfunction "A_1") (pintype "passive"))
      (node (ref "D51") (pin "1") (pinfunction "A_1") (pintype "passive"))
      (node (ref "D52") (pin "1") (pinfunction "A_1") (pintype "passive"))
      (node (ref "D53") (pin "1") (pinfunction "A_1") (pintype "passive"))
      (node (ref "D54") (pin "1") (pinfunction "A_1") (pintype "passive"))
      (node (ref "D55") (pin "1") (pinfunction "A_1") (pintype "passive"))
      (node (ref "D56") (pin "1") (pinfunction "A_1") (pintype "passive"))
      (node (ref "D57") (pin "1") (pinfunction "A_1") (pintype "passive"))
      (node (ref "D58") (pin "1") (pinfunction "A_1") (pintype "passive"))
      (node (ref "D59") (pin "1") (pinfunction "A_1") (pintype "passive"))
      (node (ref "D60") (pin "1") (pinfunction "A_1") (pintype "passive"))
    )
    (net (code "20") (name "/ROW5") (class "Default")
      (node (ref "D61") (pin "1") (pinfunction "A_1") (pintype "passive"))
      (node (ref "D62") (pin "1") (pinfunction "A_1") (pintype "passive"))
      (node (ref "D63") (pin "1") (pinfunction "A_1") (pintype "passive"))
      (node (ref "D64") (pin "1") (pinfunction "A_1") (pintype "passive"))
      (node (ref "D65") (pin "1") (pinfunction "A_1") (pintype "passive"))
      (node (ref "D66") (pin "1") (pinfunction "A_1") (pintype "passive"))
      (node (ref "D67") (pin "1") (pinfunction "A_1") (pintype "passive"))
      (node (ref "D68") (pin "1") (pinfunction "A_1") (pintype "passive"))
      (node (ref "D69") (pin "1") (pinfunction "A_1") (pintype "passive"))
      (node (ref "D70") (pin "1") (pinfunction "A_1") (pintype "passive"))
      (node (ref "D71") (pin "1") (pinfunction "A_1") (pintype "passive"))
      (node (ref "D72") (pin "1") (pinfunction "A_1") (pintype "passive"))
      (node (ref "D73") (pin "1") (pinfunction "A_1") (pintype "passive"))
      (node (ref "D74") (pin "1") (pinfunction "A_1") (pintype "passive"))
      (node (ref "D75") (pin "1") (pinfunction "A_1") (pintype "passive"))
    )
    (net (code "21") (name "Net-(D1-A-Pad2)") (class "Default")
      (node (ref "D1") (pin "2") (pinfunction "A_2") (pintype "passive"))
      (node (ref "SW*1") (pin "2") (pinfunction "2_2") (pintype "passive"))
    )
    (net (code "22") (name "Net-(D2-A-Pad2)") (class "Default")
      (node (ref "D2") (pin "2") (pinfunction "A_2") (pintype "passive"))
      (node (ref "SW*2") (pin "2") (pinfunction "2_2") (pintype "passive"))
    )
    (net (code "23") (name "Net-(D3-A-Pad2)") (class "Default")
      (node (ref "D3") (pin "2") (pinfunction "A_2") (pintype "passive"))
      (node (ref "SW*3") (pin "2") (pinfunction "2_2") (pintype "passive"))
    )
    (net (code "24") (name "Net-(D4-A-Pad2)") (class "Default")
      (node (ref "D4") (pin "2") (pinfunction "A_2") (pintype "passive"))
      (node (ref "SW*4") (pin "2") (pinfunction "2_2") (pintype "passive"))
    )
    (net (code "25") (name "Net-(D5-A-Pad2)") (class "Default")
      (node (ref "D5") (pin "2") (pinfunction "A_2") (pintype "passive"))
      (node (ref "SW*5") (pin "2") (pinfunction "2_2") (pintype "passive"))
    )
    (net (code "26") (name "Net-(D6-A-Pad2)") (class "Default")
      (node (ref "D6") (pin "2") (pinfunction "A_2") (pintype "passive"))
      (node (ref "SW*6") (pin "2") (pinfunction "2_2") (pintype "passive"))
    )
    (net (code "27") (name "Net-(D7-A-Pad2)") (class "Default")
      (node (ref "D7") (pin "2") (pinfunction "A_2") (pintype "passive"))
      (node (ref "SW*7") (pin "2") (pinfunction "2_2") (pintype "passive"))
    )
    (net (code "28") (name "Net-(D8-A-Pad2)") (class "Default")
      (node (ref "D8") (pin "2") (pinfunction "A_2") (pintype "passive"))
      (node (ref "SW*8") (pin "2") (pinfunction "2_2") (pintype "passive"))
    )
    (net (code "29") (name "Net-(D9-A-Pad2)") (class "Default")
      (node (ref "D9") (pin "2") (pinfunction "A_2") (pintype "passive"))
      (node (ref "SW*9") (pin "2") (pinfunction "2_2") (pintype "passive"))
    )
    (net (code "30") (name "Net-(D10-A-Pad2)") (class "Default")
      (node (ref "D10") (pin "2") (pinfunction "A_2") (pintype "passive"))
      (node (ref "SW*10") (pin "2") (pinfunction "2_2") (pintype "passive"))
    )
    (net (code "31") (name "Net-(D11-A-Pad2)") (class "Default")
      (node (ref "D11") (pin "2") (pinfunction "A_2") (pintype "passive"))
      (node (ref "SW*11") (pin "2") (pinfunction "2_2") (pintype "passive"))
    )
    (net (code "32") (name "Net-(D12-A-Pad2)") (class "Default")
      (node (ref "D12") (pin "2") (pinfunction "A_2") (pintype "passive"))
      (node (ref "SW*12") (pin "2") (pinfunction "2_2") (pintype "passive"))
    )
    (net (code "33") (name "Net-(D13-A-Pad2)") (class "Default")
      (node (ref "D13") (pin "2") (pinfunction "A_2") (pintype "passive"))
      (node (ref "SW*13") (pin "2") (pinfunction "2_2") (pintype "passive"))
    )
    (net (code "34") (name "Net-(D14-A-Pad2)") (class "Default")
      (node (ref "D14") (pin "2") (pinfunction "A_2") (pintype "passive"))
      (node (ref "SW*14") (pin "2") (pinfunction "2_2") (pintype "passive"))
    )
    (net (code "35") (name "Net-(D15-A-Pad2)") (class "Default")
      (node (ref "D15") (pin "2") (pinfunction "A_2") (pintype "passive"))
      (node (ref "SW*15") (pin "2") (pinfunction "2_2") (pintype "passive"))
    )
    (net (code "36") (name "Net-(D16-A-Pad2)") (class "Default")
      (node (ref "D16") (pin "2") (pinfunction "A_2") (pintype "passive"))
      (node (ref "SW*16") (pin "2") (pinfunction "2_2") (pintype "passive"))
    )
    (net (code "37") (name "Net-(D17-A-Pad2)") (class "Default")
      (node (ref "D17") (pin "2") (pinfunction "A_2") (pintype "passive"))
      (node (ref "SW*17") (pin "2") (pinfunction "2_2") (pintype "passive"))
    )
    (net (code "38") (name "Net-(D18-A-Pad2)") (class "Default")
      (node (ref "D18") (pin "2") (pinfunction "A_2") (pintype "passive"))
      (node (ref "SW*18") (pin "2") (pinfunction "2_2") (pintype "passive"))
    )
    (net (code "39") (name "Net-(D19-A-Pad2)") (class "Default")
      (node (ref "D19") (pin "2") (pinfunction "A_2") (pintype "passive"))
      (node (ref "SW*19") (pin "2") (pinfunction "2_2") (pintype "passive"))
    )
    (net (code "40") (name "Net-(D20-A-Pad2)") (class "Default")
      (node (ref "D20") (pin "2") (pinfunction "A_2") (pintype "passive"))
      (node (ref "SW*20") (pin "2") (pinfunction "2_2") (pintype "passive"))
    )
    (net (code "41") (name "Net-(D21-A-Pad2)") (class "Default")
      (node (ref "D21") (pin "2") (pinfunction "A_2") (pintype "passive"))
      (node (ref "SW*21") (pin "2") (pinfunction "2_2") (pintype "passive"))
    )
    (net (code "42") (name "Net-(D22-A-Pad2)") (class "Default")
      (node (ref "D22") (pin "2") (pinfunction "A_2") (pintype "passive"))
      (node (ref "SW*22") (pin "2") (pinfunction "2_2") (pintype "passive"))
    )
    (net (code "43") (name "Net-(D23-A-Pad2)") (class "Default")
      (node (ref "D23") (pin "2") (pinfunction "A_2") (pintype "passive"))
      (node (ref "SW*23") (pin "2") (pinfunction "2_2") (pintype "passive"))
    )
    (net (code "44") (name "Net-(D24-A-Pad2)") (class "Default")
      (node (ref "D24") (pin "2") (pinfunction "A_2") (pintype "passive"))
      (node (ref "SW*24") (pin "2") (pinfunction "2_2") (pintype "passive"))
    )
    (net (code "45") (name "Net-(D25-A-Pad2)") (class "Default")
      (node (ref "D25") (pin "2") (pinfunction "A_2") (pintype "passive"))
      (node (ref "SW*25") (pin "2") (pinfunction "2_2") (pintype "passive"))
    )
    (net (code "46") (name "Net-(D26-A-Pad2)") (class "Default")
      (node (ref "D26") (pin "2") (pinfunction "A_2") (pintype "passive"))
      (node (ref "SW*26") (pin "2") (pinfunction "2_2") (pintype "passive"))
    )
    (net (code "47") (name "Net-(D27-A-Pad2)") (class "Default")
      (node (ref "D27") (pin "2") (pinfunction "A_2") (pintype "passive"))
      (node (ref "SW*27") (pin "2") (pinfunction "2_2") (pintype "passive"))
    )
    (net (code "48") (name "Net-(D28-A-Pad2)") (class "Default")
      (node (ref "D28") (pin "2") (pinfunction "A_2") (pintype "passive"))
      (node (ref "SW*28") (pin "2") (pinfunction "2_2") (pintype "passive"))
    )
    (net (code "49") (name "Net-(D29-A-Pad2)") (class "Default")
      (node (ref "D29") (pin "2") (pinfunction "A_2") (pintype "passive"))
      (node (ref "SW*29") (pin "2") (pinfunction "2_2") (pintype "passive"))
    )
    (net (code "50") (name "Net-(D30-A-Pad2)") (class "Default")
      (node (ref "D30") (pin "2") (pinfunction "A_2") (pintype "passive"))
      (node (ref "SW*30") (pin "2") (pinfunction "2_2") (pintype "passive"))
    )
    (net (code "51") (name "Net-(D31-A-Pad2)") (class "Default")
      (node (ref "D31") (pin "2") (pinfunction "A_2") (pintype "passive"))
      (node (ref "SW*31") (pin "2") (pinfunction "2_2") (pintype "passive"))
    )
    (net (code "52") (name "Net-(D32-A-Pad2)") (class "Default")
      (node (ref "D32") (pin "2") (pinfunction "A_2") (pintype "passive"))
      (node (ref "SW*32") (pin "2") (pinfunction "2_2") (pintype "passive"))
    )
    (net (code "53") (name "Net-(D33-A-Pad2)") (class "Default")
      (node (ref "D33") (pin "2") (pinfunction "A_2") (pintype "passive"))
      (node (ref "SW*33") (pin "2") (pinfunction "2_2") (pintype "passive"))
    )
    (net (code "54") (name "Net-(D34-A-Pad2)") (class "Default")
      (node (ref "D34") (pin "2") (pinfunction "A_2") (pintype "passive"))
      (node (ref "SW*34") (pin "2") (pinfunction "2_2") (pintype "passive"))
    )
    (net (code "55") (name "Net-(D35-A-Pad2)") (class "Default")
      (node (ref "D35") (pin "2") (pinfunction "A_2") (pintype "passive"))
      (node (ref "SW*35") (pin "2") (pinfunction "2_2") (pintype "passive"))
    )
    (net (code "56") (name "Net-(D36-A-Pad2)") (class "Default")
      (node (ref "D36") (pin "2") (pinfunction "A_2") (pintype "passive"))
      (node (ref "SW*36") (pin "2") (pinfunction "2_2") (pintype "passive"))
    )
    (net (code "57") (name "Net-(D37-A-Pad2)") (class "Default")
      (node (ref "D37") (pin "2") (pinfunction "A_2") (pintype "passive"))
      (node (ref "SW*37") (pin "2") (pinfunction "2_2") (pintype "passive"))
    )
    (net (code "58") (name "Net-(D38-A-Pad2)") (class "Default")
      (node (ref "D38") (pin "2") (pinfunction "A_2") (pintype "passive"))
      (node (ref "SW*38") (pin "2") (pinfunction "2_2") (pintype "passive"))
    )
    (net (code "59") (name "Net-(D39-A-Pad2)") (class "Default")
      (node (ref "D39") (pin "2") (pinfunction "A_2") (pintype "passive"))
      (node (ref "SW*39") (pin "2") (pinfunction "2_2") (pintype "passive"))
    )
    (net (code "60") (name "Net-(D40-A-Pad2)") (class "Default")
      (node (ref "D40") (pin "2") (pinfunction "A_2") (pintype "passive"))
      (node (ref "SW*40") (pin "2") (pinfunction "2_2") (pintype "passive"))
    )
    (net (code "61") (name "Net-(D41-A-Pad2)") (class "Default")
      (node (ref "D41") (pin "2") (pinfunction "A_2") (pintype "passive"))
      (node (ref "SW*41") (pin "2") (pinfunction "2_2") (pintype "passive"))
    )
    (net (code "62") (name "Net-(D42-A-Pad2)") (class "Default")
      (node (ref "D42") (pin "2") (pinfunction "A_2") (pintype "passive"))
      (node (ref "SW*42") (pin "2") (pinfunction "2_2") (pintype "passive"))
    )
    (net (code "63") (name "Net-(D43-A-Pad2)") (class "Default")
      (node (ref "D43") (pin "2") (pinfunction "A_2") (pintype "passive"))
      (node (ref "SW*43") (pin "2") (pinfunction "2_2") (pintype "passive"))
    )
    (net (code "64") (name "Net-(D44-A-Pad2)") (class "Default")
      (node (ref "D44") (pin "2") (pinfunction "A_2") (pintype "passive"))
      (node (ref "SW*44") (pin "2") (pinfunction "2_2") (pintype "passive"))
    )
    (net (code "65") (name "Net-(D45-A-Pad2)") (class "Default")
      (node (ref "D45") (pin "2") (pinfunction "A_2") (pintype "passive"))
      (node (ref "SW*45") (pin "2") (pinfunction "2_2") (pintype "passive"))
    )
    (net (code "66") (name "Net-(D46-A-Pad2)") (class "Default")
      (node (ref "D46") (pin "2") (pinfunction "A_2") (pintype "passive"))
      (node (ref "SW*46") (pin "2") (pinfunction "2_2") (pintype "passive"))
    )
    (net (code "67") (name "Net-(D47-A-Pad2)") (class "Default")
      (node (ref "D47") (pin "2") (pinfunction "A_2") (pintype "passive"))
      (node (ref "SW*47") (pin "2") (pinfunction "2_2") (pintype "passive"))
    )
    (net (code "68") (name "Net-(D48-A-Pad2)") (class "Default")
      (node (ref "D48") (pin "2") (pinfunction "A_2") (pintype "passive"))
      (node (ref "SW*48") (pin "2") (pinfunction "2_2") (pintype "passive"))
    )
    (net (code "69") (name "Net-(D49-A-Pad2)") (class "Default")
      (node (ref "D49") (pin "2") (pinfunction "A_2") (pintype "passive"))
      (node (ref "SW*49") (pin "2") (pinfunction "2_2") (pintype "passive"))
    )
    (net (code "70") (name "Net-(D50-A-Pad2)") (class "Default")
      (node (ref "D50") (pin "2") (pinfunction "A_2") (pintype "passive"))
      (node (ref "SW*50") (pin "2") (pinfunction "2_2") (pintype "passive"))
    )
    (net (code "71") (name "Net-(D51-A-Pad2)") (class "Default")
      (node (ref "D51") (pin "2") (pinfunction "A_2") (pintype "passive"))
      (node (ref "SW*51") (pin "2") (pinfunction "2_2") (pintype "passive"))
    )
    (net (code "72") (name "Net-(D52-A-Pad2)") (class "Default")
      (node (ref "D52") (pin "2") (pinfunction "A_2") (pintype "passive"))
      (node (ref "SW*52") (pin "2") (pinfunction "2_2") (pintype "passive"))
    )
    (net (code "73") (name "Net-(D53-A-Pad2)") (class "Default")
      (node (ref "D53") (pin "2") (pinfunction "A_2") (pintype "passive"))
      (node (ref "SW*53") (pin "2") (pinfunction "2_2") (pintype "passive"))
    )
    (net (code "74") (name "Net-(D54-A-Pad2)") (class "Default")
      (node (ref "D54") (pin "2") (pinfunction "A_2") (pintype "passive"))
      (node (ref "SW*54") (pin "2") (pinfunction "2_2") (pintype "passive"))
    )
    (net (code "75") (name "Net-(D55-A-Pad2)") (class "Default")
      (node (ref "D55") (pin "2") (pinfunction "A_2") (pintype "passive"))
      (node (ref "SW*55") (pin "2") (pinfunction "2_2") (pintype "passive"))
    )
    (net (code "76") (name "Net-(D56-A-Pad2)") (class "Default")
      (node (ref "D56") (pin "2") (pinfunction "A_2") (pintype "passive"))
      (node (ref "SW*56") (pin "2") (pinfunction "2_2") (pintype "passive"))
    )
    (net (code "77") (name "Net-(D57-A-Pad2)") (class "Default")
      (node (ref "D57") (pin "2") (pinfunction "A_2") (pintype "passive"))
      (node (ref "SW*57") (pin "2") (pinfunction "2_2") (pintype "passive"))
    )
    (net (code "78") (name "Net-(D58-A-Pad2)") (class "Default")
      (node (ref "D58") (pin "2") (pinfunction "A_2") (pintype "passive"))
      (node (ref "SW*58") (pin "2") (pinfunction "2_2") (pintype "passive"))
    )
    (net (code "79") (name "Net-(D59-A-Pad2)") (class "Default")
      (node (ref "D59") (pin "2") (pinfunction "A_2") (pintype "passive"))
      (node (ref "SW*59") (pin "2") (pinfunction "2_2") (pintype "passive"))
    )
    (net (code "80") (name "Net-(D60-A-Pad2)") (class "Default")
      (node (ref "D60") (pin "2") (pinfunction "A_2") (pintype "passive"))
      (node (ref "SW*60") (pin "2") (pinfunction "2_2") (pintype "passive"))
    )
    (net (code "81") (name "Net-(D61-A-Pad2)") (class "Default")
      (node (ref "D61") (pin "2") (pinfunction "A_2") (pintype "passive"))
      (node (ref "SW*61") (pin "2") (pinfunction "2_2") (pintype "passive"))
    )
    (net (code "82") (name "Net-(D62-A-Pad2)") (class "Default")
      (node (ref "D62") (pin "2") (pinfunction "A_2") (pintype "passive"))
      (node (ref "SW*62") (pin "2") (pinfunction "2_2") (pintype "passive"))
    )
    (net (code "83") (name "Net-(D63-A-Pad2)") (class "Default")
      (node (ref "D63") (pin "2") (pinfunction "A_2") (pintype "passive"))
      (node (ref "SW*63") (pin "2") (pinfunction "2_2") (pintype "passive"))
    )
    (net (code "84") (name "Net-(D64-A-Pad2)") (class "Default")
      (node (ref "D64") (pin "2") (pinfunction "A_2") (pintype "passive"))
      (node (ref "SW*64") (pin "2") (pinfunction "2_2") (pintype "passive"))
    )
    (net (code "85") (name "Net-(D65-A-Pad2)") (class "Default")
      (node (ref "D65") (pin "2") (pinfunction "A_2") (pintype "passive"))
      (node (ref "SW*65") (pin "2") (pinfunction "2_2") (pintype "passive"))
    )
    (net (code "86") (name "Net-(D66-A-Pad2)") (class "Default")
      (node (ref "D66") (pin "2") (pinfunction "A_2") (pintype "passive"))
      (node (ref "SW*66") (pin "2") (pinfunction "2_2") (pintype "passive"))
    )
    (net (code "87") (name "Net-(D67-A-Pad2)") (class "Default")
      (node (ref "D67") (pin "2") (pinfunction "A_2") (pintype "passive"))
      (node (ref "SW*67") (pin "2") (pinfunction "2_2") (pintype "passive"))
    )
    (net (code "88") (name "Net-(D68-A-Pad2)") (class "Default")
      (node (ref "D68") (pin "2") (pinfunction "A_2") (pintype "passive"))
      (node (ref "SW*68") (pin "2") (pinfunction "2_2") (pintype "passive"))
    )
    (net (code "89") (name "Net-(D69-A-Pad2)") (class "Default")
      (node (ref "D69") (pin "2") (pinfunction "A_2") (pintype "passive"))
      (node (ref "SW*69") (pin "2") (pinfunction "2_2") (pintype "passive"))
    )
    (net (code "90") (name "Net-(D70-A-Pad2)") (class "Default")
      (node (ref "D70") (pin "2") (pinfunction "A_2") (pintype "passive"))
      (node (ref "SW*70") (pin "2") (pinfunction "2_2") (pintype "passive"))
    )
    (net (code "91") (name "Net-(D71-A-Pad2)") (class "Default")
      (node (ref "D71") (pin "2") (pinfunction "A_2") (pintype "passive"))
      (node (ref "SW*71") (pin "2") (pinfunction "2_2") (pintype "passive"))
    )
    (net (code "92") (name "Net-(D72-A-Pad2)") (class "Default")
      (node (ref "D72") (pin "2") (pinfunction "A_2") (pintype "passive"))
      (node (ref "SW*72") (pin "2") (pinfunction "2_2") (pintype "passive"))
    )
    (net (code "93") (name "Net-(D73-A-Pad2)") (class "Default")
      (node (ref "D73") (pin "2") (pinfunction "A_2") (pintype "passive"))
      (node (ref "SW*73") (pin "2") (pinfunction "2_2") (pintype "passive"))
    )
    (net (code "94") (name "Net-(D74-A-Pad2)") (class "Default")
      (node (ref "D74") (pin "2") (pinfunction "A_2") (pintype "passive"))
      (node (ref "SW*74") (pin "2") (pinfunction "2_2") (pintype "passive"))
    )
    (net (code "95") (name "Net-(D75-A-Pad2)") (class "Default")
      (node (ref "D75") (pin "2") (pinfunction "A_2") (pintype "passive"))
      (node (ref "SW*75") (pin "2") (pinfunction "2_2") (pintype "passive"))
    )
  )
)
